# AOA-sensor-board.net
KiCad netlist of a schematic drawn in EAGLE
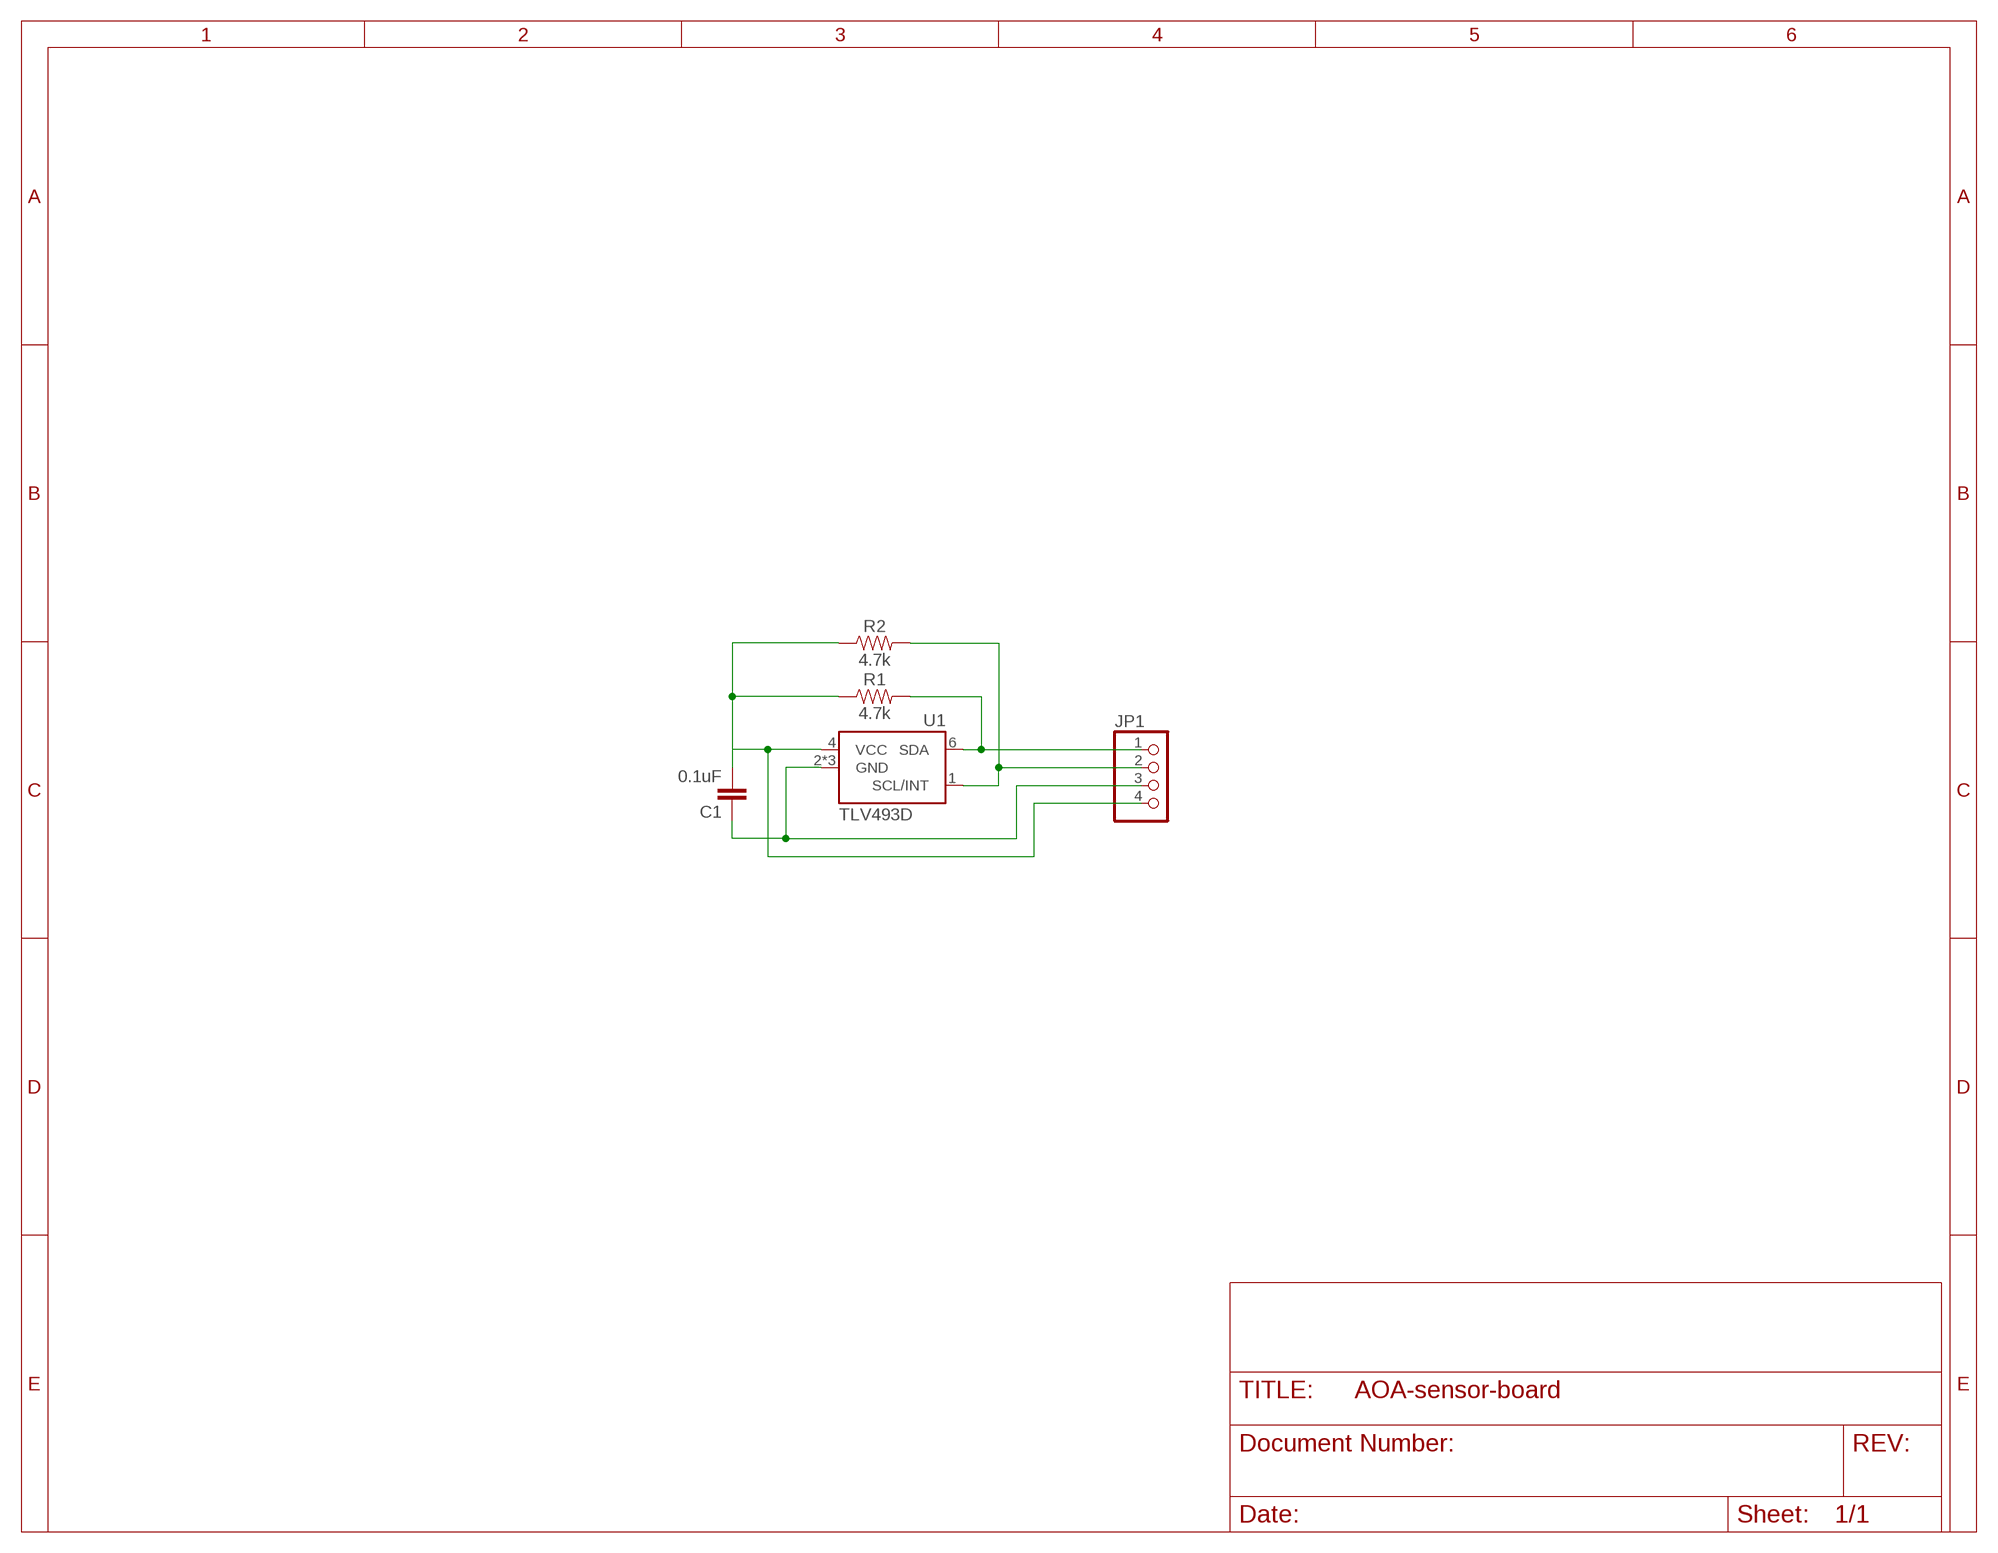
[diagram p0: schematic, sheet 1]

(export (version "E")
  (design (tool "Eeschema 10.0.6"))
  (components
    (comp (ref "C1")
      (value "0.1uF")
      (footprint "eagle-import:0603")
      (libsource (lib "eagle-import") (part "0.1UF-0603-25V-(+80/-20%)"))
    )
    (comp (ref "JP1")
      (value "PINHD-1X4")
      (footprint "eagle-import:1X04")
      (libsource (lib "eagle-import") (part "PINHD-1X4"))
    )
    (comp (ref "R1")
      (value "4.7k")
      (footprint "eagle-import:0603")
      (libsource (lib "eagle-import") (part "4.7KOHM-0603-1/10W-1%"))
    )
    (comp (ref "R2")
      (value "4.7k")
      (footprint "eagle-import:0603")
      (libsource (lib "eagle-import") (part "4.7KOHM-0603-1/10W-1%"))
    )
    (comp (ref "U1")
      (value "TLV493D")
      (footprint "eagle-import:TSOP-6")
      (libsource (lib "eagle-import") (part "TLV493D"))
    )
  )
  (nets
    (net (code "1") (name "Net-(C1-Pad1)") (class "Default")
      (node (ref "C1") (pin "1") (pinfunction "1_1") (pintype "passive"))
      (node (ref "JP1") (pin "3") (pinfunction "3_3") (pintype "passive"))
      (node (ref "U1") (pin "2") (pinfunction "GND_2") (pintype "bidirectional"))
      (node (ref "U1") (pin "3") (pinfunction "GND_3") (pintype "bidirectional"))
      (node (ref "U1") (pin "5") (pinfunction "GND_5") (pintype "bidirectional"))
    )
    (net (code "2") (name "Net-(U1-SCL{slash}INT)") (class "Default")
      (node (ref "JP1") (pin "2") (pinfunction "2_2") (pintype "passive"))
      (node (ref "R2") (pin "2") (pinfunction "2_2") (pintype "passive"))
      (node (ref "U1") (pin "1") (pinfunction "SCL/INT_1") (pintype "bidirectional"))
    )
    (net (code "3") (name "Net-(U1-SDA)") (class "Default")
      (node (ref "JP1") (pin "1") (pinfunction "1_1") (pintype "passive"))
      (node (ref "R1") (pin "2") (pinfunction "2_2") (pintype "passive"))
      (node (ref "U1") (pin "6") (pinfunction "SDA_6") (pintype "bidirectional"))
    )
    (net (code "4") (name "Net-(U1-VCC)") (class "Default")
      (node (ref "C1") (pin "2") (pinfunction "2_2") (pintype "passive"))
      (node (ref "JP1") (pin "4") (pinfunction "4_4") (pintype "passive"))
      (node (ref "R1") (pin "1") (pinfunction "1_1") (pintype "passive"))
      (node (ref "R2") (pin "1") (pinfunction "1_1") (pintype "passive"))
      (node (ref "U1") (pin "4") (pinfunction "VCC_4") (pintype "bidirectional"))
    )
  )
)
